# ProPrj_usb__2025-12-14-12-44-50.net
KiCad netlist of a schematic drawn in EasyEDA Pro
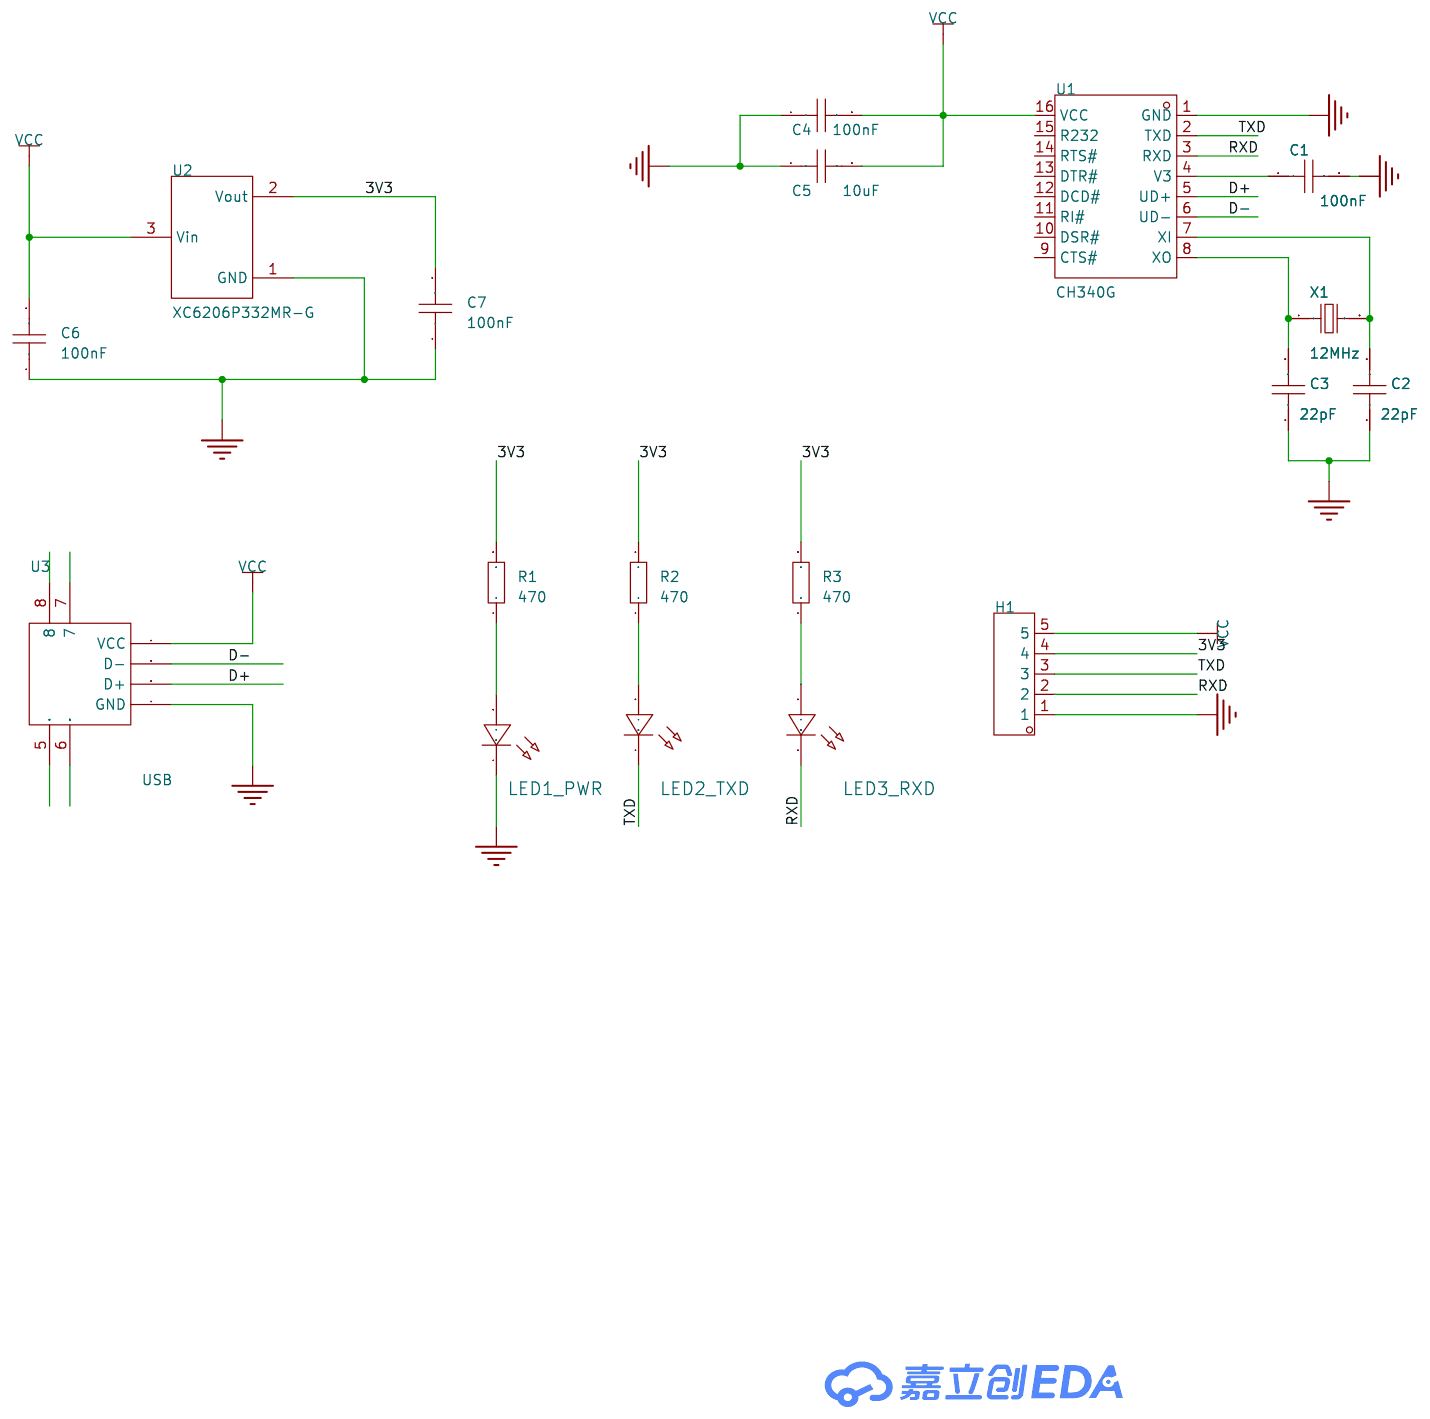
[diagram p0: schematic sheet]

(export (version "E")
  (design (tool "Eeschema 10.0.6"))
  (components
    (comp (ref "C1")
      (value "100nF")
      (footprint "easyedapro:C0603")
      (libsource (lib "easyedapro") (part "Capacitance"))
    )
    (comp (ref "C2")
      (value "22pF")
      (footprint "easyedapro:C0603")
      (libsource (lib "easyedapro") (part "Capacitance"))
    )
    (comp (ref "C3")
      (value "22pF")
      (footprint "easyedapro:C0603")
      (libsource (lib "easyedapro") (part "Capacitance"))
    )
    (comp (ref "C4")
      (value "100nF")
      (footprint "easyedapro:C0603")
      (libsource (lib "easyedapro") (part "Capacitance"))
    )
    (comp (ref "C5")
      (value "10uF")
      (footprint "easyedapro:C0603")
      (libsource (lib "easyedapro") (part "Capacitance"))
    )
    (comp (ref "C6")
      (value "100nF")
      (footprint "easyedapro:C0603")
      (libsource (lib "easyedapro") (part "Capacitance"))
    )
    (comp (ref "C7")
      (value "100nF")
      (footprint "easyedapro:C0603")
      (libsource (lib "easyedapro") (part "Capacitance"))
    )
    (comp (ref "H1")
      (value "~")
      (footprint "easyedapro:HDR-TH_5P-P2.54-V-M")
      (libsource (lib "easyedapro") (part "MTP125-1105S1"))
    )
    (comp (ref "LED1_PWR")
      (value "~")
      (footprint "easyedapro:LED_0603")
      (libsource (lib "easyedapro") (part "LED_R"))
    )
    (comp (ref "LED2_TXD")
      (value "~")
      (footprint "easyedapro:LED_0603")
      (libsource (lib "easyedapro") (part "LED_R"))
    )
    (comp (ref "LED3_RXD")
      (value "~")
      (footprint "easyedapro:LED_0603")
      (libsource (lib "easyedapro") (part "LED_R"))
    )
    (comp (ref "R1") (value "470") (footprint "easyedapro:R0603") (libsource (lib "easyedapro") (part "电阻")))
    (comp (ref "R2") (value "470") (footprint "easyedapro:R0603") (libsource (lib "easyedapro") (part "电阻")))
    (comp (ref "R3") (value "470") (footprint "easyedapro:R0603") (libsource (lib "easyedapro") (part "电阻")))
    (comp (ref "U1")
      (value "CH340G")
      (footprint "easyedapro:SOIC-16_L9.9-W3.9-P1.27-LS6.0-BL")
      (description "应用功能:USB转UART;接口协议:USB 2.0;数据速率:2Mbps;")
      (fields (field (name "Manufacturer") "WCH(南京沁恒)"))
      (libsource (lib "easyedapro") (part "CH340G"))
    )
    (comp (ref "U2")
      (value "XC6206P332MR-G")
      (footprint "easyedapro:SOT-23-3_L2.9-W1.6-P1.90-LS2.8-BR")
      (description "输出类型:固定;工作电压:6V;输出电压:3.3V;输出电流:200mA;电源纹波抑制比(PSRR):-;输出极性:正极;")
      (fields (field (name "Manufacturer") "TOREX(特瑞仕)"))
      (libsource (lib "easyedapro") (part "XC6206P332MR"))
    )
    (comp (ref "U3")
      (value "USB")
      (footprint "easyedapro:USB-SMD_USB_1")
      (libsource (lib "easyedapro") (part "USB"))
    )
    (comp (ref "X1")
      (value "12MHz")
      (footprint "easyedapro:CRYSTAL-SMD_L5.0-W3.2")
      (description "晶振类型:贴片晶振;频率:12MHz;常温频差:±20ppm;负载电容:20pF;频率稳定度:±30ppm;")
      (fields
        (field (name "Manufacturer Part") "XC53G2-12.000-F20LJDT")
        (field (name "Manufacturer") "HCI(杭晶)")
      )
      (libsource (lib "easyedapro") (part "XC53G2-12.000-F20LJDT"))
    )
  )
  (nets
    (net (code "1") (name "/3V3") (class "Default")
      (node (ref "C7") (pin "2") (pinfunction "2_2") (pintype "input"))
      (node (ref "H1") (pin "4") (pinfunction "4_4") (pintype "unspecified"))
      (node (ref "R1") (pin "2") (pinfunction "2_2") (pintype "input"))
      (node (ref "R2") (pin "2") (pinfunction "2_2") (pintype "input"))
      (node (ref "R3") (pin "2") (pinfunction "2_2") (pintype "input"))
      (node (ref "U2") (pin "2") (pinfunction "Vout_2") (pintype "unspecified"))
    )
    (net (code "2") (name "/D+") (class "Default")
      (node (ref "U1") (pin "5") (pinfunction "UD+_5") (pintype "unspecified"))
      (node (ref "U3") (pin "3") (pinfunction "D+_3") (pintype "input"))
    )
    (net (code "3") (name "/D-") (class "Default")
      (node (ref "U1") (pin "6") (pinfunction "UD-_6") (pintype "unspecified"))
      (node (ref "U3") (pin "2") (pinfunction "D-_2") (pintype "input"))
    )
    (net (code "4") (name "/RXD") (class "Default")
      (node (ref "H1") (pin "2") (pinfunction "2_2") (pintype "unspecified"))
      (node (ref "LED3_RXD") (pin "1") (pinfunction "C_1") (pintype "input"))
      (node (ref "U1") (pin "3") (pinfunction "RXD_3") (pintype "unspecified"))
    )
    (net (code "5") (name "/TXD") (class "Default")
      (node (ref "H1") (pin "3") (pinfunction "3_3") (pintype "unspecified"))
      (node (ref "LED2_TXD") (pin "1") (pinfunction "C_1") (pintype "input"))
      (node (ref "U1") (pin "2") (pinfunction "TXD_2") (pintype "unspecified"))
    )
    (net (code "6") (name "GND") (class "Default")
      (node (ref "C1") (pin "2") (pinfunction "2_2") (pintype "input"))
      (node (ref "C2") (pin "1") (pinfunction "1_1") (pintype "input"))
      (node (ref "C3") (pin "1") (pinfunction "1_1") (pintype "input"))
      (node (ref "C4") (pin "1") (pinfunction "1_1") (pintype "input"))
      (node (ref "C5") (pin "1") (pinfunction "1_1") (pintype "input"))
      (node (ref "C6") (pin "1") (pinfunction "1_1") (pintype "input"))
      (node (ref "C7") (pin "1") (pinfunction "1_1") (pintype "input"))
      (node (ref "H1") (pin "1") (pinfunction "1_1") (pintype "unspecified"))
      (node (ref "LED1_PWR") (pin "1") (pinfunction "C_1") (pintype "input"))
      (node (ref "U1") (pin "1") (pinfunction "GND_1") (pintype "unspecified"))
      (node (ref "U2") (pin "1") (pinfunction "GND_1") (pintype "unspecified"))
      (node (ref "U3") (pin "4") (pinfunction "GND_4") (pintype "input"))
    )
    (net (code "7") (name "Net-(LED1_PWR-A)") (class "Default")
      (node (ref "LED1_PWR") (pin "2") (pinfunction "A_2") (pintype "input"))
      (node (ref "R1") (pin "1") (pinfunction "1_1") (pintype "input"))
    )
    (net (code "8") (name "Net-(LED2_TXD-A)") (class "Default")
      (node (ref "LED2_TXD") (pin "2") (pinfunction "A_2") (pintype "input"))
      (node (ref "R2") (pin "1") (pinfunction "1_1") (pintype "input"))
    )
    (net (code "9") (name "Net-(LED3_RXD-A)") (class "Default")
      (node (ref "LED3_RXD") (pin "2") (pinfunction "A_2") (pintype "input"))
      (node (ref "R3") (pin "1") (pinfunction "1_1") (pintype "input"))
    )
    (net (code "10") (name "Net-(U1-V3)") (class "Default")
      (node (ref "C1") (pin "1") (pinfunction "1_1") (pintype "input"))
      (node (ref "U1") (pin "4") (pinfunction "V3_4") (pintype "unspecified"))
    )
    (net (code "11") (name "Net-(U1-XI)") (class "Default")
      (node (ref "C2") (pin "2") (pinfunction "2_2") (pintype "input"))
      (node (ref "U1") (pin "7") (pinfunction "XI_7") (pintype "unspecified"))
      (node (ref "X1") (pin "2") (pinfunction "2_2") (pintype "unspecified"))
    )
    (net (code "12") (name "Net-(U1-XO)") (class "Default")
      (node (ref "C3") (pin "2") (pinfunction "2_2") (pintype "input"))
      (node (ref "U1") (pin "8") (pinfunction "XO_8") (pintype "unspecified"))
      (node (ref "X1") (pin "1") (pinfunction "1_1") (pintype "unspecified"))
    )
    (net (code "13") (name "VCC") (class "Default")
      (node (ref "C4") (pin "2") (pinfunction "2_2") (pintype "input"))
      (node (ref "C5") (pin "2") (pinfunction "2_2") (pintype "input"))
      (node (ref "C6") (pin "2") (pinfunction "2_2") (pintype "input"))
      (node (ref "H1") (pin "5") (pinfunction "5_5") (pintype "unspecified"))
      (node (ref "U1") (pin "16") (pinfunction "VCC_16") (pintype "unspecified"))
      (node (ref "U2") (pin "3") (pinfunction "Vin_3") (pintype "unspecified"))
      (node (ref "U3") (pin "1") (pinfunction "VCC_1") (pintype "input"))
    )
    (net (code "14") (name "unconnected-(U1-CTS#-Pad9)") (class "Default")
      (node (ref "U1") (pin "9") (pinfunction "CTS#_9") (pintype "unspecified"))
    )
    (net (code "15") (name "unconnected-(U1-DCD#-Pad12)") (class "Default")
      (node (ref "U1") (pin "12") (pinfunction "DCD#_12") (pintype "unspecified"))
    )
    (net (code "16") (name "unconnected-(U1-DSR#-Pad10)") (class "Default")
      (node (ref "U1") (pin "10") (pinfunction "DSR#_10") (pintype "unspecified"))
    )
    (net (code "17") (name "unconnected-(U1-DTR#-Pad13)") (class "Default")
      (node (ref "U1") (pin "13") (pinfunction "DTR#_13") (pintype "unspecified"))
    )
    (net (code "18") (name "unconnected-(U1-R232-Pad15)") (class "Default")
      (node (ref "U1") (pin "15") (pinfunction "R232_15") (pintype "unspecified"))
    )
    (net (code "19") (name "unconnected-(U1-RI#-Pad11)") (class "Default")
      (node (ref "U1") (pin "11") (pinfunction "RI#_11") (pintype "unspecified"))
    )
    (net (code "20") (name "unconnected-(U1-RTS#-Pad14)") (class "Default")
      (node (ref "U1") (pin "14") (pinfunction "RTS#_14") (pintype "unspecified"))
    )
    (net (code "21") (name "unconnected-(U3-Pad7)") (class "Default")
      (node (ref "U3") (pin "7") (pinfunction "7_7") (pintype "unspecified"))
    )
    (net (code "22") (name "unconnected-(U3-Pad8)") (class "Default")
      (node (ref "U3") (pin "8") (pinfunction "8_8") (pintype "unspecified"))
    )
    (net (code "23") (name "unconnected-(U3-SH1-Pad5)") (class "Default")
      (node (ref "U3") (pin "5") (pinfunction "SH1_5") (pintype "unspecified"))
    )
    (net (code "24") (name "unconnected-(U3-SH2-Pad6)") (class "Default")
      (node (ref "U3") (pin "6") (pinfunction "SH2_6") (pintype "unspecified"))
    )
  )
)
